# lipo-booster.net
KiCad netlist of a schematic drawn in EAGLE
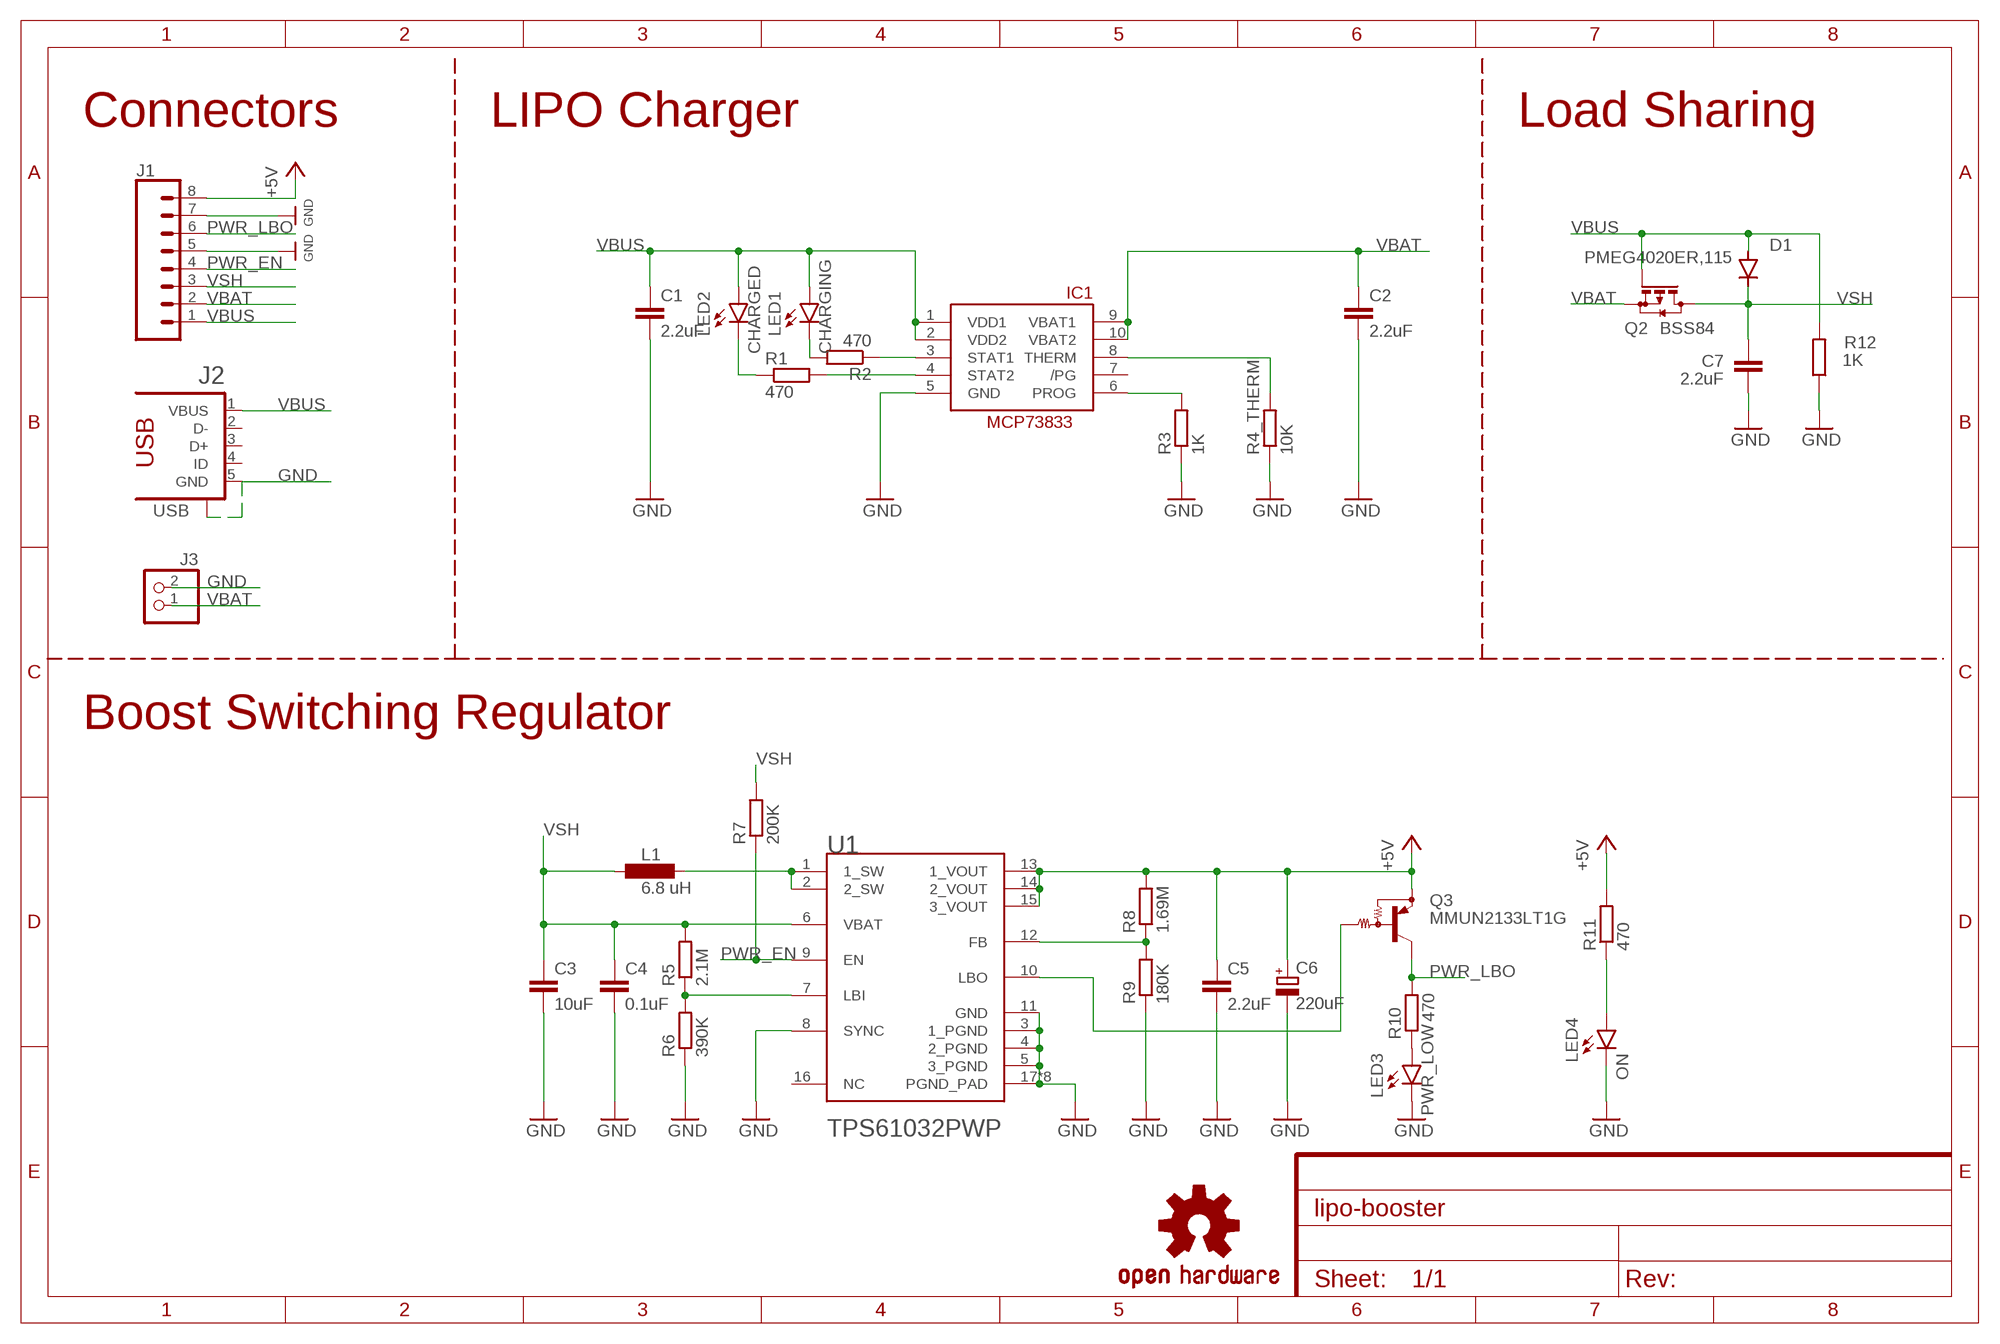
[diagram p0: schematic, sheet 1]

(export (version "E")
  (design (tool "Eeschema 10.0.6"))
  (components
    (comp (ref "C1")
      (value "2.2uF")
      (footprint "eagle-import:C0603")
      (libsource (lib "eagle-import") (part "C-EUC0603"))
    )
    (comp (ref "C2")
      (value "2.2uF")
      (footprint "eagle-import:C0603")
      (libsource (lib "eagle-import") (part "C-EUC0603"))
    )
    (comp (ref "C3")
      (value "10uF")
      (footprint "eagle-import:C0603")
      (libsource (lib "eagle-import") (part "C-EUC0603"))
    )
    (comp (ref "C4")
      (value "0.1uF")
      (footprint "eagle-import:C0603")
      (libsource (lib "eagle-import") (part "C-EUC0603"))
    )
    (comp (ref "C5")
      (value "2.2uF")
      (footprint "eagle-import:C0603")
      (libsource (lib "eagle-import") (part "C-EUC0603"))
    )
    (comp (ref "C6")
      (value "220uF")
      (footprint "eagle-import:CT3528")
      (libsource (lib "eagle-import") (part "CPOL-EUCT3528"))
    )
    (comp (ref "C7")
      (value "2.2uF")
      (footprint "eagle-import:C0603")
      (libsource (lib "eagle-import") (part "C-EUC0603"))
    )
    (comp (ref "D1")
      (value "PMEG4020ER,115")
      (footprint "eagle-import:SOD-123_MINI-SMA")
      (fields (field (name "SPICEPREFIX") "D"))
      (libsource (lib "eagle-import") (part "CGRM400-G1"))
    )
    (comp (ref "IC1")
      (value "MCP73833-UN")
      (footprint "eagle-import:MSOP10")
      (libsource (lib "eagle-import") (part "MCP73833-UN"))
    )
    (comp (ref "J1")
      (value "CONN_08\"")
      (footprint "eagle-import:1X08")
      (libsource (lib "eagle-import") (part "CONN_08{dblquote}"))
    )
    (comp (ref "J2")
      (value "USB")
      (footprint "eagle-import:1981584-1")
      (libsource (lib "eagle-import") (part "1981584-1"))
    )
    (comp (ref "J3")
      (value "JST_2PIN-THM")
      (footprint "eagle-import:JST-PH-2-THM")
      (libsource (lib "eagle-import") (part "JST_2PIN-THM"))
    )
    (comp (ref "L1")
      (value "6.8 uH")
      (footprint "eagle-import:POWER-CHOKE_WE-TPC")
      (libsource (lib "eagle-import") (part "L-EUWE-TPC"))
    )
    (comp (ref "LED1")
      (value "CHARGING")
      (footprint "eagle-import:CHIP-LED0603")
      (libsource (lib "eagle-import") (part "LEDCHIP-LED0603"))
    )
    (comp (ref "LED2")
      (value "CHARGED")
      (footprint "eagle-import:CHIP-LED0603")
      (libsource (lib "eagle-import") (part "LEDCHIP-LED0603"))
    )
    (comp (ref "LED3")
      (value "PWR_LOW")
      (footprint "eagle-import:CHIP-LED0603")
      (libsource (lib "eagle-import") (part "LEDCHIP-LED0603"))
    )
    (comp (ref "LED4")
      (value "ON")
      (footprint "eagle-import:CHIP-LED0603")
      (libsource (lib "eagle-import") (part "LEDCHIP-LED0603"))
    )
    (comp (ref "LOGO1")
      (value "OSHW-LOGOS")
      (footprint "eagle-import:OSHW-LOGO-S")
      (libsource (lib "eagle-import") (part "OSHW-LOGOS"))
    )
    (comp (ref "Q2")
      (value "BSS84")
      (footprint "eagle-import:SOT23")
      (libsource (lib "eagle-import") (part "BSS84"))
    )
    (comp (ref "Q3")
      (value "MMUN2133LT1G")
      (footprint "eagle-import:SC59-BEC")
      (libsource (lib "eagle-import") (part "MUN2114T1"))
    )
    (comp (ref "R1")
      (value "470")
      (footprint "eagle-import:R0603")
      (libsource (lib "eagle-import") (part "R-EU_R0603"))
    )
    (comp (ref "R2")
      (value "470")
      (footprint "eagle-import:R0603")
      (libsource (lib "eagle-import") (part "R-EU_R0603"))
    )
    (comp (ref "R3")
      (value "1K")
      (footprint "eagle-import:R0603")
      (libsource (lib "eagle-import") (part "R-EU_R0603"))
    )
    (comp (ref "R4_THERM")
      (value "10K")
      (footprint "eagle-import:R0603")
      (libsource (lib "eagle-import") (part "R-EU_R0603"))
    )
    (comp (ref "R5")
      (value "2.1M")
      (footprint "eagle-import:R0603")
      (libsource (lib "eagle-import") (part "R-EU_R0603"))
    )
    (comp (ref "R6")
      (value "390K")
      (footprint "eagle-import:R0603")
      (libsource (lib "eagle-import") (part "R-EU_R0603"))
    )
    (comp (ref "R7")
      (value "200K")
      (footprint "eagle-import:R0603")
      (libsource (lib "eagle-import") (part "R-EU_R0603"))
    )
    (comp (ref "R8")
      (value "1.69M")
      (footprint "eagle-import:R0603")
      (libsource (lib "eagle-import") (part "R-EU_R0603"))
    )
    (comp (ref "R9")
      (value "180K")
      (footprint "eagle-import:R0603")
      (libsource (lib "eagle-import") (part "R-EU_R0603"))
    )
    (comp (ref "R10")
      (value "470")
      (footprint "eagle-import:R0603")
      (libsource (lib "eagle-import") (part "R-EU_R0603"))
    )
    (comp (ref "R11")
      (value "470")
      (footprint "eagle-import:R0603")
      (libsource (lib "eagle-import") (part "R-EU_R0603"))
    )
    (comp (ref "R12")
      (value "1K")
      (footprint "eagle-import:R0603")
      (libsource (lib "eagle-import") (part "R-EU_R0603"))
    )
    (comp (ref "U1")
      (value "TEXAS_INSTRUMENTS_TPS61032PWPTEXAS_INSTRUMENTS_TPS61030PWP_0_0")
      (footprint "eagle-import:TEXAS_INSTRUMENTS_TPS61032PWP_0")
      (fields
        (field (name "DIGIKEY_PART_NUMBER") "296-27006-5-ND")
        (field (name "MF") "Texas Instruments")
        (field (name "MOUSER_PART_NUMBER") "595-TPS61030PWP")
      )
      (libsource (lib "eagle-import") (part "TEXAS_INSTRUMENTS_TPS61032PWPTEXAS_INSTRUMENTS_TPS61030PWP_0_0"))
    )
  )
  (nets
    (net (code "1") (name "+5V") (class "Default")
      (node (ref "C5") (pin "1") (pinfunction "1_1") (pintype "passive"))
      (node (ref "C6") (pin "-") (pinfunction "+_-") (pintype "passive"))
      (node (ref "J1") (pin "8") (pinfunction "8_8") (pintype "passive"))
      (node (ref "Q3") (pin "E") (pinfunction "E_E") (pintype "passive"))
      (node (ref "R11") (pin "2") (pinfunction "2_2") (pintype "passive"))
      (node (ref "R8") (pin "2") (pinfunction "2_2") (pintype "passive"))
      (node (ref "U1") (pin "13") (pinfunction "1_VOUT_13") (pintype "bidirectional"))
      (node (ref "U1") (pin "14") (pinfunction "2_VOUT_14") (pintype "bidirectional"))
      (node (ref "U1") (pin "15") (pinfunction "3_VOUT_15") (pintype "bidirectional"))
    )
    (net (code "2") (name "/PWR_EN") (class "Default")
      (node (ref "J1") (pin "4") (pinfunction "4_4") (pintype "passive"))
      (node (ref "R7") (pin "1") (pinfunction "1_1") (pintype "passive"))
      (node (ref "U1") (pin "9") (pinfunction "EN_9") (pintype "bidirectional"))
    )
    (net (code "3") (name "/PWR_LBO") (class "Default")
      (node (ref "J1") (pin "6") (pinfunction "6_6") (pintype "passive"))
      (node (ref "Q3") (pin "C") (pinfunction "C_C") (pintype "passive"))
      (node (ref "R10") (pin "2") (pinfunction "2_2") (pintype "passive"))
    )
    (net (code "4") (name "/VBAT") (class "Default")
      (node (ref "C2") (pin "1") (pinfunction "1_1") (pintype "passive"))
      (node (ref "IC1") (pin "10") (pinfunction "VBAT2_10") (pintype "output"))
      (node (ref "IC1") (pin "9") (pinfunction "VBAT1_9") (pintype "output"))
      (node (ref "J1") (pin "2") (pinfunction "2_2") (pintype "passive"))
      (node (ref "J3") (pin "1") (pinfunction "2_1") (pintype "passive"))
      (node (ref "Q2") (pin "2") (pinfunction "S_2") (pintype "passive"))
    )
    (net (code "5") (name "/VBUS") (class "Default")
      (node (ref "C1") (pin "1") (pinfunction "1_1") (pintype "passive"))
      (node (ref "D1") (pin "A") (pinfunction "A_A") (pintype "passive"))
      (node (ref "IC1") (pin "1") (pinfunction "VDD1_1") (pintype "power_in"))
      (node (ref "IC1") (pin "2") (pinfunction "VDD2_2") (pintype "power_in"))
      (node (ref "J1") (pin "1") (pinfunction "1_1") (pintype "passive"))
      (node (ref "J2") (pin "1") (pinfunction "VBUS_1") (pintype "passive"))
      (node (ref "LED1") (pin "A") (pinfunction "A_A") (pintype "passive"))
      (node (ref "LED2") (pin "A") (pinfunction "A_A") (pintype "passive"))
      (node (ref "Q2") (pin "1") (pinfunction "G_1") (pintype "passive"))
      (node (ref "R12") (pin "2") (pinfunction "2_2") (pintype "passive"))
    )
    (net (code "6") (name "/VSH") (class "Default")
      (node (ref "C3") (pin "1") (pinfunction "1_1") (pintype "passive"))
      (node (ref "C4") (pin "1") (pinfunction "1_1") (pintype "passive"))
      (node (ref "C7") (pin "1") (pinfunction "1_1") (pintype "passive"))
      (node (ref "D1") (pin "C") (pinfunction "C_C") (pintype "passive"))
      (node (ref "J1") (pin "3") (pinfunction "3_3") (pintype "passive"))
      (node (ref "L1") (pin "2") (pinfunction "2_2") (pintype "passive"))
      (node (ref "Q2") (pin "3") (pinfunction "D_3") (pintype "passive"))
      (node (ref "R5") (pin "2") (pinfunction "2_2") (pintype "passive"))
      (node (ref "R7") (pin "2") (pinfunction "2_2") (pintype "passive"))
      (node (ref "U1") (pin "6") (pinfunction "VBAT_6") (pintype "bidirectional"))
    )
    (net (code "7") (name "GND") (class "Default")
      (node (ref "C1") (pin "2") (pinfunction "2_2") (pintype "passive"))
      (node (ref "C2") (pin "2") (pinfunction "2_2") (pintype "passive"))
      (node (ref "C3") (pin "2") (pinfunction "2_2") (pintype "passive"))
      (node (ref "C4") (pin "2") (pinfunction "2_2") (pintype "passive"))
      (node (ref "C5") (pin "2") (pinfunction "2_2") (pintype "passive"))
      (node (ref "C6") (pin "+") (pinfunction "-_+") (pintype "passive"))
      (node (ref "C7") (pin "2") (pinfunction "2_2") (pintype "passive"))
      (node (ref "IC1") (pin "5") (pinfunction "GND_5") (pintype "power_in"))
      (node (ref "J1") (pin "5") (pinfunction "5_5") (pintype "passive"))
      (node (ref "J1") (pin "7") (pinfunction "7_7") (pintype "passive"))
      (node (ref "J2") (pin "5") (pinfunction "GND_5") (pintype "passive"))
      (node (ref "J2") (pin "S1") (pinfunction "S1_S1") (pintype "passive"))
      (node (ref "J3") (pin "2") (pinfunction "1_2") (pintype "passive"))
      (node (ref "LED3") (pin "C") (pinfunction "C_C") (pintype "passive"))
      (node (ref "LED4") (pin "C") (pinfunction "C_C") (pintype "passive"))
      (node (ref "R12") (pin "1") (pinfunction "1_1") (pintype "passive"))
      (node (ref "R3") (pin "1") (pinfunction "1_1") (pintype "passive"))
      (node (ref "R4_THERM") (pin "1") (pinfunction "1_1") (pintype "passive"))
      (node (ref "R6") (pin "1") (pinfunction "1_1") (pintype "passive"))
      (node (ref "R9") (pin "1") (pinfunction "1_1") (pintype "passive"))
      (node (ref "U1") (pin "11") (pinfunction "GND_11") (pintype "bidirectional"))
      (node (ref "U1") (pin "17") (pinfunction "PGND_PAD_17") (pintype "bidirectional"))
      (node (ref "U1") (pin "3") (pinfunction "1_PGND_3") (pintype "bidirectional"))
      (node (ref "U1") (pin "4") (pinfunction "2_PGND_4") (pintype "bidirectional"))
      (node (ref "U1") (pin "5") (pinfunction "3_PGND_5") (pintype "bidirectional"))
      (node (ref "U1") (pin "8") (pinfunction "SYNC_8") (pintype "bidirectional"))
      (node (ref "U1") (pin "PAD_1") (pinfunction "PGND_PAD_PAD_1") (pintype "bidirectional"))
      (node (ref "U1") (pin "PAD_2") (pinfunction "PGND_PAD_PAD_2") (pintype "bidirectional"))
      (node (ref "U1") (pin "PAD_3") (pinfunction "PGND_PAD_PAD_3") (pintype "bidirectional"))
      (node (ref "U1") (pin "PAD_4") (pinfunction "PGND_PAD_PAD_4") (pintype "bidirectional"))
      (node (ref "U1") (pin "PAD_5") (pinfunction "PGND_PAD_PAD_5") (pintype "bidirectional"))
      (node (ref "U1") (pin "PAD_6") (pinfunction "PGND_PAD_PAD_6") (pintype "bidirectional"))
      (node (ref "U1") (pin "SMD_33") (pinfunction "PGND_PAD_SMD_33") (pintype "bidirectional"))
    )
    (net (code "8") (name "Net-(IC1-PROG)") (class "Default")
      (node (ref "IC1") (pin "6") (pinfunction "PROG_6") (pintype "input"))
      (node (ref "R3") (pin "2") (pinfunction "2_2") (pintype "passive"))
    )
    (net (code "9") (name "Net-(IC1-STAT1)") (class "Default")
      (node (ref "IC1") (pin "3") (pinfunction "STAT1_3") (pintype "passive"))
      (node (ref "R2") (pin "1") (pinfunction "1_1") (pintype "passive"))
    )
    (net (code "10") (name "Net-(IC1-STAT2)") (class "Default")
      (node (ref "IC1") (pin "4") (pinfunction "STAT2_4") (pintype "passive"))
      (node (ref "R1") (pin "2") (pinfunction "2_2") (pintype "passive"))
    )
    (net (code "11") (name "Net-(IC1-THERM)") (class "Default")
      (node (ref "IC1") (pin "8") (pinfunction "THERM_8") (pintype "bidirectional"))
      (node (ref "R4_THERM") (pin "2") (pinfunction "2_2") (pintype "passive"))
    )
    (net (code "12") (name "Net-(LED1-PadC)") (class "Default")
      (node (ref "LED1") (pin "C") (pinfunction "C_C") (pintype "passive"))
      (node (ref "R2") (pin "2") (pinfunction "2_2") (pintype "passive"))
    )
    (net (code "13") (name "Net-(LED2-PadC)") (class "Default")
      (node (ref "LED2") (pin "C") (pinfunction "C_C") (pintype "passive"))
      (node (ref "R1") (pin "1") (pinfunction "1_1") (pintype "passive"))
    )
    (net (code "14") (name "Net-(LED3-PadA)") (class "Default")
      (node (ref "LED3") (pin "A") (pinfunction "A_A") (pintype "passive"))
      (node (ref "R10") (pin "1") (pinfunction "1_1") (pintype "passive"))
    )
    (net (code "15") (name "Net-(LED4-PadA)") (class "Default")
      (node (ref "LED4") (pin "A") (pinfunction "A_A") (pintype "passive"))
      (node (ref "R11") (pin "1") (pinfunction "1_1") (pintype "passive"))
    )
    (net (code "16") (name "Net-(U1-1_SW)") (class "Default")
      (node (ref "L1") (pin "1") (pinfunction "1_1") (pintype "passive"))
      (node (ref "U1") (pin "1") (pinfunction "1_SW_1") (pintype "bidirectional"))
      (node (ref "U1") (pin "2") (pinfunction "2_SW_2") (pintype "bidirectional"))
    )
    (net (code "17") (name "Net-(U1-FB)") (class "Default")
      (node (ref "R8") (pin "1") (pinfunction "1_1") (pintype "passive"))
      (node (ref "R9") (pin "2") (pinfunction "2_2") (pintype "passive"))
      (node (ref "U1") (pin "12") (pinfunction "FB_12") (pintype "bidirectional"))
    )
    (net (code "18") (name "Net-(U1-LBI)") (class "Default")
      (node (ref "R5") (pin "1") (pinfunction "1_1") (pintype "passive"))
      (node (ref "R6") (pin "2") (pinfunction "2_2") (pintype "passive"))
      (node (ref "U1") (pin "7") (pinfunction "LBI_7") (pintype "bidirectional"))
    )
    (net (code "19") (name "Net-(U1-LBO)") (class "Default")
      (node (ref "Q3") (pin "B") (pinfunction "B_B") (pintype "passive"))
      (node (ref "U1") (pin "10") (pinfunction "LBO_10") (pintype "bidirectional"))
    )
    (net (code "20") (name "unconnected-(IC1-{slash}PG-Pad7)") (class "Default")
      (node (ref "IC1") (pin "7") (pinfunction "/PG_7") (pintype "passive"))
    )
    (net (code "21") (name "unconnected-(J2-D+-Pad3)") (class "Default")
      (node (ref "J2") (pin "3") (pinfunction "D+_3") (pintype "passive"))
    )
    (net (code "22") (name "unconnected-(J2-D--Pad2)") (class "Default")
      (node (ref "J2") (pin "2") (pinfunction "D-_2") (pintype "passive"))
    )
    (net (code "23") (name "unconnected-(J2-ID-Pad4)") (class "Default")
      (node (ref "J2") (pin "4") (pinfunction "ID_4") (pintype "passive"))
    )
    (net (code "24") (name "unconnected-(U1-NC-Pad16)") (class "Default")
      (node (ref "U1") (pin "16") (pinfunction "NC_16") (pintype "bidirectional"))
    )
  )
)
